# Cell_SARA-G350-02S.net
KiCad netlist of a schematic drawn in Altium Designer
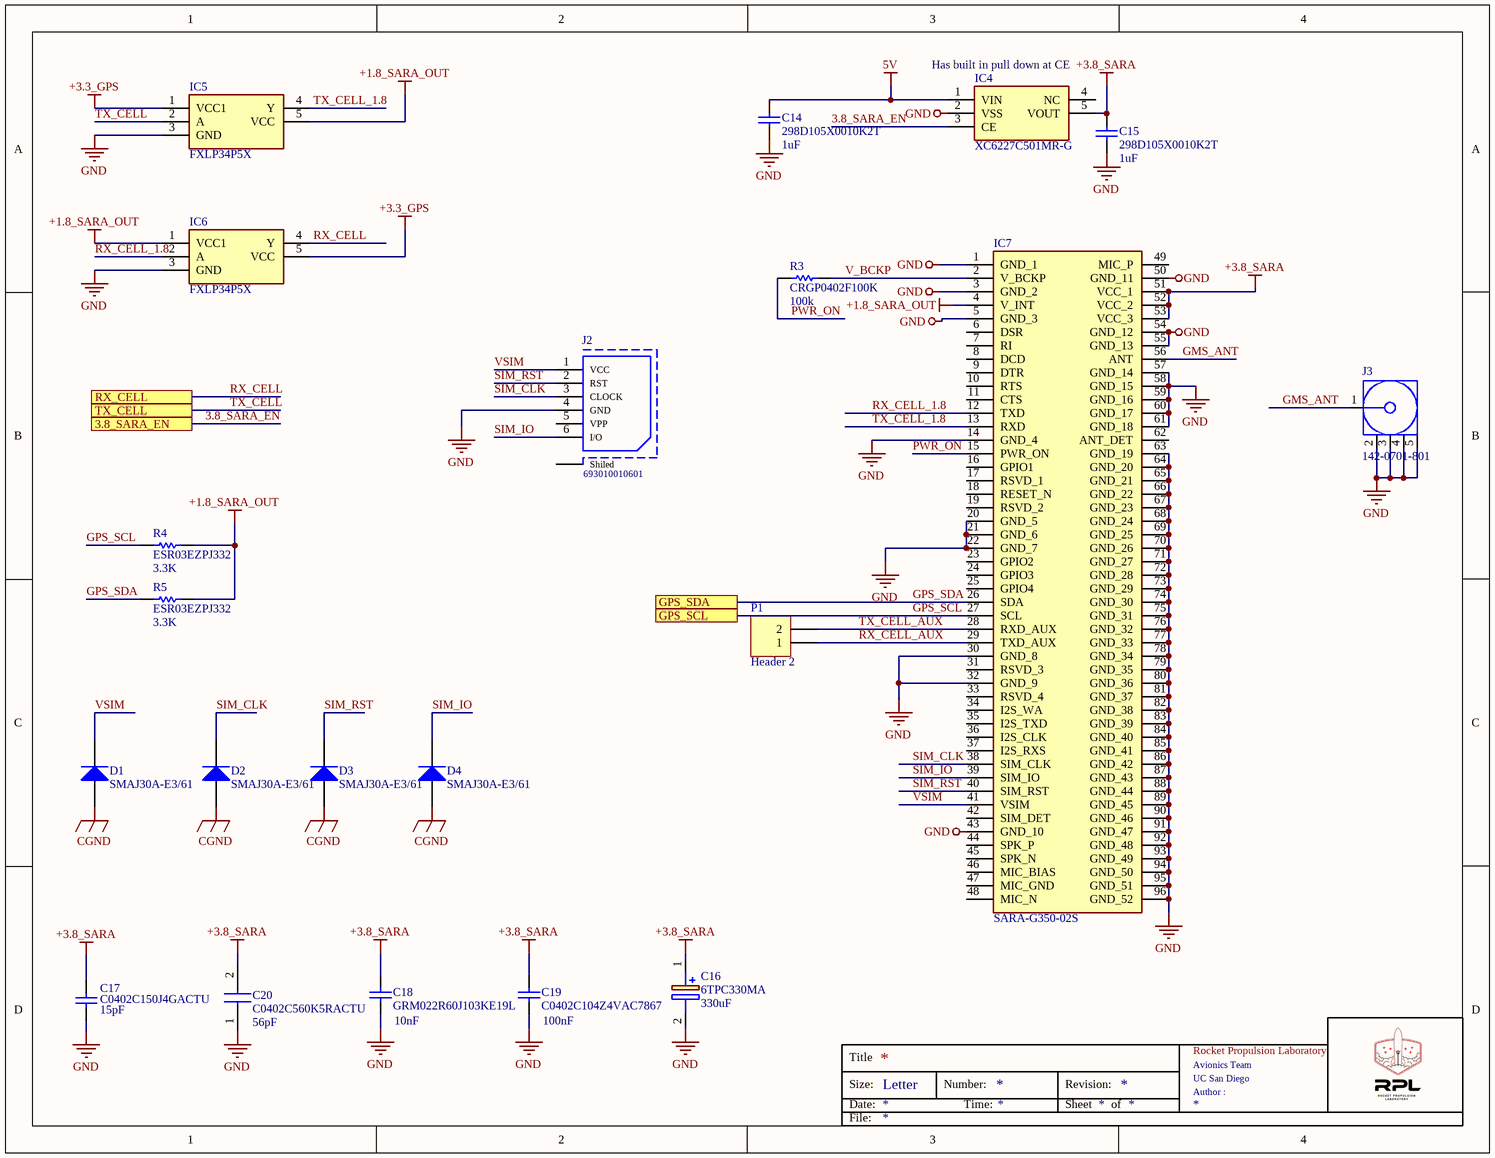
[diagram p0: Cell_SARA-G350-02S.SchDoc]

(export (version "E")
  (design (tool "Eeschema 10.0.6"))
  (components
    (comp (ref "C14")
      (value "298D105X0010K2T")
      (footprint "0402")
      (description "Capacitor")
      (fields (field (name "ALTIUM_VALUE") "1uF") (field (name "PUBLISHER") "Altium Limited"))
      (libsource (lib "Miscellaneous Devices") (part "Cap"))
    )
    (comp (ref "C15")
      (value "298D105X0010K2T")
      (footprint "0402")
      (description "Capacitor")
      (fields (field (name "ALTIUM_VALUE") "1uF") (field (name "PUBLISHER") "Altium Limited"))
      (libsource (lib "Miscellaneous Devices") (part "Cap"))
    )
    (comp (ref "C16")
      (value "6TPC330MA")
      (footprint "PcbLib1:CAPPM7343X200N")
      (description "Capacitor Polarised")
      (fields
        (field (name "MOUSER PART NUMBER") "667-6TPC330MA")
        (field (name "RS PART NUMBER") "7887368P")
        (field (name "SPEC") "330uF")
      )
      (libsource (lib "*") (part "6TPC330MA"))
    )
    (comp (ref "C17")
      (value "C0402C150J4GACTU")
      (footprint "CAPC0402(1005)60_L")
      (description "CAP 15pF 16V ±5% 0402 (1005 Metric) Thickness 0.6mm SMD")
      (fields (field (name "ALTIUM_VALUE") "15pF") (field (name "TOLERANCE") "Â±5%"))
      (libsource (lib "Altium Content Vault") (part "CAP"))
    )
    (comp (ref "C18")
      (value "GRM022R60J103KE19L")
      (footprint "CAPC1005X55X25NL05T10")
      (fields (field (name "MANUFACTURER") "Murata") (field (name "SPEC") "10nF"))
      (libsource (lib "Altium Content Vault") (part "CAP"))
    )
    (comp (ref "C19")
      (value "C0402C104Z4VAC7867")
      (footprint "CAPC1005X60X30LL05T10")
      (fields (field (name "MANUFACTURER") "Kemet") (field (name "SPEC") "100nF"))
      (libsource (lib "Altium Content Vault") (part "CAP"))
    )
    (comp (ref "C20")
      (value "C0402C560K5RACTU")
      (footprint "PcbLib1:CAPC1005X55N")
      (description "Capacitor")
      (fields (field (name "MOUSER PART NUMBER") "80-C0402C560K5RACTU") (field (name "SPEC") "56pF"))
      (libsource (lib "*") (part "C0402C560K5RACTU"))
    )
    (comp (ref "D1")
      (value "SMAJ30A-E3/61")
      (footprint "VISH-DO-214AC-2_N")
      (fields (field (name "MANUFACTURER") "Vishay Semiconductor"))
      (libsource (lib "Altium Content Vault") (part "VISH-K1A2-2"))
    )
    (comp (ref "D2")
      (value "SMAJ30A-E3/61")
      (footprint "VISH-DO-214AC-2_N")
      (fields (field (name "MANUFACTURER") "Vishay Semiconductor"))
      (libsource (lib "Altium Content Vault") (part "VISH-K1A2-2"))
    )
    (comp (ref "D3")
      (value "SMAJ30A-E3/61")
      (footprint "VISH-DO-214AC-2_N")
      (fields (field (name "MANUFACTURER") "Vishay Semiconductor"))
      (libsource (lib "Altium Content Vault") (part "VISH-K1A2-2"))
    )
    (comp (ref "D4")
      (value "SMAJ30A-E3/61")
      (footprint "VISH-DO-214AC-2_N")
      (fields (field (name "MANUFACTURER") "Vishay Semiconductor"))
      (libsource (lib "Altium Content Vault") (part "VISH-K1A2-2"))
    )
    (comp (ref "IC4")
      (value "XC6227C501MR-G")
      (footprint "PcbLib1:SOT95P280X130-5N")
      (description "Integrated Circuit")
      (fields (field (name "MOUSER PART NUMBER") "865-XC6227C501MR-G"))
      (libsource (lib "*") (part "XC6227C501MR-G"))
    )
    (comp (ref "IC5")
      (value "FXLP34P5X")
      (footprint "PcbLib1:SOT65P210X110-5N")
      (description "Integrated Circuit")
      (fields (field (name "MOUSER PART NUMBER") "512-FXLP34P5X"))
      (libsource (lib "*") (part "FXLP34P5X"))
    )
    (comp (ref "IC6")
      (value "FXLP34P5X")
      (footprint "PcbLib1:SOT65P210X110-5N")
      (description "Integrated Circuit")
      (fields (field (name "MOUSER PART NUMBER") "512-FXLP34P5X"))
      (libsource (lib "*") (part "FXLP34P5X"))
    )
    (comp (ref "IC7")
      (value "SARA-G350-02S")
      (footprint "PcbLib1:SARA-G350_1")
      (description "Integrated Circuit")
      (libsource (lib "*") (part "SARA-G350-02S"))
    )
    (comp (ref "J2")
      (value "693010010601")
      (footprint "693010010601")
      (description "WR-CRD Mini SIM Card Connector Header")
      (fields (field (name "MANUFACTURER") "Wurth Elektronik") (field (name "PUBLISHER") "WurthElektronik"))
      (libsource (lib "Altium Content Vault") (part "WE-CN-SD-6-SW-1S"))
    )
    (comp (ref "J3")
      (value "142-0701-801")
      (footprint "CINC-142-0701-801_V")
      (description "SMA End Launch Jack Receptacle, 50 Ohm, 0 to 18 GHz, -65 to 165 degC, 5-Pin SMD, RoHS, Bulk")
      (fields (field (name "MANUFACTURER") "EmersonConnectivitySolutions"))
      (libsource (lib "Altium Content Vault") (part "CN-S-4F-RF5"))
    )
    (comp (ref "P1")
      (value "Header 2")
      (footprint "HDR1X2")
      (description "Header, 2-Pin")
      (fields (field (name "PUBLISHER") "Altium Limited"))
      (libsource (lib "Miscellaneous Connectors") (part "Header 2"))
    )
    (comp (ref "R3")
      (value "CRGP0402F100K")
      (footprint "0402")
      (description "Resistor")
      (fields (field (name "ALTIUM_VALUE") "100k") (field (name "PUBLISHER") "Altium Limited"))
      (libsource (lib "Miscellaneous Devices") (part "Res1"))
    )
    (comp (ref "R4")
      (value "ESR03EZPJ332")
      (footprint "1608[0603]")
      (description "Resistor")
      (fields (field (name "ALTIUM_VALUE") "3.3K") (field (name "PUBLISHER") "Altium Limited"))
      (libsource (lib "Miscellaneous Devices") (part "Res1"))
    )
    (comp (ref "R5")
      (value "ESR03EZPJ332")
      (footprint "1608[0603]")
      (description "Resistor")
      (fields (field (name "ALTIUM_VALUE") "3.3K") (field (name "PUBLISHER") "Altium Limited"))
      (libsource (lib "Miscellaneous Devices") (part "Res1"))
    )
  )
  (nets
    (net (code "1") (name "+1.8_SARA_OUT") (class "Default")
      (node (ref "IC5") (pin "5") (pinfunction "VCC_5") (pintype "passive"))
      (node (ref "IC6") (pin "1") (pinfunction "VCC1_1") (pintype "passive"))
      (node (ref "IC7") (pin "4") (pinfunction "V_INT_4") (pintype "passive"))
      (node (ref "R4") (pin "2") (pinfunction "2_2") (pintype "passive"))
      (node (ref "R5") (pin "2") (pinfunction "2_2") (pintype "passive"))
    )
    (net (code "2") (name "+3.3_GPS") (class "Default")
      (node (ref "IC5") (pin "1") (pinfunction "VCC1_1") (pintype "passive"))
      (node (ref "IC6") (pin "5") (pinfunction "VCC_5") (pintype "passive"))
    )
    (net (code "3") (name "+3.8_SARA") (class "Default")
      (node (ref "C15") (pin "2") (pinfunction "2_2") (pintype "passive"))
      (node (ref "C16") (pin "1") (pinfunction "+_1") (pintype "passive"))
      (node (ref "C17") (pin "2") (pinfunction "2_2") (pintype "passive"))
      (node (ref "C18") (pin "2") (pinfunction "2_2") (pintype "passive"))
      (node (ref "C19") (pin "2") (pinfunction "2_2") (pintype "passive"))
      (node (ref "C20") (pin "2") (pinfunction "2_2") (pintype "passive"))
      (node (ref "IC4") (pin "5") (pinfunction "VOUT_5") (pintype "passive"))
      (node (ref "IC7") (pin "51") (pinfunction "VCC_1_51") (pintype "passive"))
      (node (ref "IC7") (pin "52") (pinfunction "VCC_2_52") (pintype "passive"))
      (node (ref "IC7") (pin "53") (pinfunction "VCC_3_53") (pintype "passive"))
    )
    (net (code "4") (name "/3.8_SARA_EN") (class "Default")
      (node (ref "IC4") (pin "3") (pinfunction "CE_3") (pintype "passive"))
    )
    (net (code "5") (name "/GMS_ANT") (class "Default")
      (node (ref "IC7") (pin "56") (pinfunction "ANT_56") (pintype "passive"))
      (node (ref "J3") (pin "1") (pinfunction "1_1") (pintype "passive"))
    )
    (net (code "6") (name "/GPS_SCL") (class "Default")
      (node (ref "IC7") (pin "27") (pinfunction "SCL_27") (pintype "passive"))
      (node (ref "R4") (pin "1") (pinfunction "1_1") (pintype "passive"))
    )
    (net (code "7") (name "/GPS_SDA") (class "Default")
      (node (ref "IC7") (pin "26") (pinfunction "SDA_26") (pintype "passive"))
      (node (ref "R5") (pin "1") (pinfunction "1_1") (pintype "passive"))
    )
    (net (code "8") (name "/PWR_ON") (class "Default")
      (node (ref "IC7") (pin "15") (pinfunction "PWR_ON_15") (pintype "passive"))
      (node (ref "R3") (pin "2") (pinfunction "2_2") (pintype "passive"))
    )
    (net (code "9") (name "/RX_CELL") (class "Default")
      (node (ref "IC6") (pin "4") (pinfunction "Y_4") (pintype "passive"))
    )
    (net (code "10") (name "/RX_CELL_1.8") (class "Default")
      (node (ref "IC6") (pin "2") (pinfunction "A_2") (pintype "passive"))
      (node (ref "IC7") (pin "12") (pinfunction "TXD_12") (pintype "passive"))
    )
    (net (code "11") (name "/RX_CELL_AUX") (class "Default")
      (node (ref "IC7") (pin "29") (pinfunction "TXD_AUX_29") (pintype "passive"))
      (node (ref "P1") (pin "1") (pinfunction "1_1") (pintype "passive"))
    )
    (net (code "12") (name "/SIM_CLK") (class "Default")
      (node (ref "D2") (pin "1") (pinfunction "K_1") (pintype "passive"))
      (node (ref "IC7") (pin "38") (pinfunction "SIM_CLK_38") (pintype "passive"))
      (node (ref "J2") (pin "3") (pinfunction "CLOCK_3") (pintype "passive"))
    )
    (net (code "13") (name "/SIM_IO") (class "Default")
      (node (ref "D4") (pin "1") (pinfunction "K_1") (pintype "passive"))
      (node (ref "IC7") (pin "39") (pinfunction "SIM_IO_39") (pintype "passive"))
      (node (ref "J2") (pin "6") (pinfunction "I/O_6") (pintype "passive"))
    )
    (net (code "14") (name "/SIM_RST") (class "Default")
      (node (ref "D3") (pin "1") (pinfunction "K_1") (pintype "passive"))
      (node (ref "IC7") (pin "40") (pinfunction "SIM_RST_40") (pintype "passive"))
      (node (ref "J2") (pin "2") (pinfunction "RST_2") (pintype "passive"))
    )
    (net (code "15") (name "/TX_CELL") (class "Default")
      (node (ref "IC5") (pin "2") (pinfunction "A_2") (pintype "passive"))
    )
    (net (code "16") (name "/TX_CELL_1.8") (class "Default")
      (node (ref "IC5") (pin "4") (pinfunction "Y_4") (pintype "passive"))
      (node (ref "IC7") (pin "13") (pinfunction "RXD_13") (pintype "passive"))
    )
    (net (code "17") (name "/TX_CELL_AUX") (class "Default")
      (node (ref "IC7") (pin "28") (pinfunction "RXD_AUX_28") (pintype "passive"))
      (node (ref "P1") (pin "2") (pinfunction "2_2") (pintype "passive"))
    )
    (net (code "18") (name "/VSIM") (class "Default")
      (node (ref "D1") (pin "1") (pinfunction "K_1") (pintype "passive"))
      (node (ref "IC7") (pin "41") (pinfunction "VSIM_41") (pintype "passive"))
      (node (ref "J2") (pin "1") (pinfunction "VCC_1") (pintype "passive"))
    )
    (net (code "19") (name "/V_BCKP") (class "Default")
      (node (ref "IC7") (pin "2") (pinfunction "V_BCKP_2") (pintype "passive"))
      (node (ref "R3") (pin "1") (pinfunction "1_1") (pintype "passive"))
    )
    (net (code "20") (name "5V") (class "Default")
      (node (ref "C14") (pin "2") (pinfunction "2_2") (pintype "passive"))
      (node (ref "IC4") (pin "1") (pinfunction "VIN_1") (pintype "passive"))
    )
    (net (code "21") (name "CGND") (class "Default")
      (node (ref "D1") (pin "2") (pinfunction "A_2") (pintype "passive"))
      (node (ref "D2") (pin "2") (pinfunction "A_2") (pintype "passive"))
      (node (ref "D3") (pin "2") (pinfunction "A_2") (pintype "passive"))
      (node (ref "D4") (pin "2") (pinfunction "A_2") (pintype "passive"))
    )
    (net (code "22") (name "GND") (class "Default")
      (node (ref "C14") (pin "1") (pinfunction "1_1") (pintype "passive"))
      (node (ref "C15") (pin "1") (pinfunction "1_1") (pintype "passive"))
      (node (ref "C16") (pin "2") (pinfunction "-_2") (pintype "passive"))
      (node (ref "C17") (pin "1") (pinfunction "1_1") (pintype "passive"))
      (node (ref "C18") (pin "1") (pinfunction "1_1") (pintype "passive"))
      (node (ref "C19") (pin "1") (pinfunction "1_1") (pintype "passive"))
      (node (ref "C20") (pin "1") (pinfunction "1_1") (pintype "passive"))
      (node (ref "IC4") (pin "2") (pinfunction "VSS_2") (pintype "passive"))
      (node (ref "IC5") (pin "3") (pinfunction "GND_3") (pintype "passive"))
      (node (ref "IC6") (pin "3") (pinfunction "GND_3") (pintype "passive"))
      (node (ref "IC7") (pin "1") (pinfunction "GND_1_1") (pintype "passive"))
      (node (ref "IC7") (pin "14") (pinfunction "GND_4_14") (pintype "passive"))
      (node (ref "IC7") (pin "20") (pinfunction "GND_5_20") (pintype "passive"))
      (node (ref "IC7") (pin "21") (pinfunction "GND_6_21") (pintype "passive"))
      (node (ref "IC7") (pin "22") (pinfunction "GND_7_22") (pintype "passive"))
      (node (ref "IC7") (pin "3") (pinfunction "GND_2_3") (pintype "passive"))
      (node (ref "IC7") (pin "30") (pinfunction "GND_8_30") (pintype "passive"))
      (node (ref "IC7") (pin "32") (pinfunction "GND_9_32") (pintype "passive"))
      (node (ref "IC7") (pin "43") (pinfunction "GND_10_43") (pintype "passive"))
      (node (ref "IC7") (pin "5") (pinfunction "GND_3_5") (pintype "passive"))
      (node (ref "IC7") (pin "50") (pinfunction "GND_11_50") (pintype "passive"))
      (node (ref "IC7") (pin "54") (pinfunction "GND_12_54") (pintype "passive"))
      (node (ref "IC7") (pin "55") (pinfunction "GND_13_55") (pintype "passive"))
      (node (ref "IC7") (pin "57") (pinfunction "GND_14_57") (pintype "passive"))
      (node (ref "IC7") (pin "58") (pinfunction "GND_15_58") (pintype "passive"))
      (node (ref "IC7") (pin "59") (pinfunction "GND_16_59") (pintype "passive"))
      (node (ref "IC7") (pin "60") (pinfunction "GND_17_60") (pintype "passive"))
      (node (ref "IC7") (pin "61") (pinfunction "GND_18_61") (pintype "passive"))
      (node (ref "IC7") (pin "63") (pinfunction "GND_19_63") (pintype "passive"))
      (node (ref "IC7") (pin "64") (pinfunction "GND_20_64") (pintype "passive"))
      (node (ref "IC7") (pin "65") (pinfunction "GND_21_65") (pintype "passive"))
      (node (ref "IC7") (pin "66") (pinfunction "GND_22_66") (pintype "passive"))
      (node (ref "IC7") (pin "67") (pinfunction "GND_23_67") (pintype "passive"))
      (node (ref "IC7") (pin "68") (pinfunction "GND_24_68") (pintype "passive"))
      (node (ref "IC7") (pin "69") (pinfunction "GND_25_69") (pintype "passive"))
      (node (ref "IC7") (pin "70") (pinfunction "GND_26_70") (pintype "passive"))
      (node (ref "IC7") (pin "71") (pinfunction "GND_27_71") (pintype "passive"))
      (node (ref "IC7") (pin "72") (pinfunction "GND_28_72") (pintype "passive"))
      (node (ref "IC7") (pin "73") (pinfunction "GND_29_73") (pintype "passive"))
      (node (ref "IC7") (pin "74") (pinfunction "GND_30_74") (pintype "passive"))
      (node (ref "IC7") (pin "75") (pinfunction "GND_31_75") (pintype "passive"))
      (node (ref "IC7") (pin "76") (pinfunction "GND_32_76") (pintype "passive"))
      (node (ref "IC7") (pin "77") (pinfunction "GND_33_77") (pintype "passive"))
      (node (ref "IC7") (pin "78") (pinfunction "GND_34_78") (pintype "passive"))
      (node (ref "IC7") (pin "79") (pinfunction "GND_35_79") (pintype "passive"))
      (node (ref "IC7") (pin "80") (pinfunction "GND_36_80") (pintype "passive"))
      (node (ref "IC7") (pin "81") (pinfunction "GND_37_81") (pintype "passive"))
      (node (ref "IC7") (pin "82") (pinfunction "GND_38_82") (pintype "passive"))
      (node (ref "IC7") (pin "83") (pinfunction "GND_39_83") (pintype "passive"))
      (node (ref "IC7") (pin "84") (pinfunction "GND_40_84") (pintype "passive"))
      (node (ref "IC7") (pin "85") (pinfunction "GND_41_85") (pintype "passive"))
      (node (ref "IC7") (pin "86") (pinfunction "GND_42_86") (pintype "passive"))
      (node (ref "IC7") (pin "87") (pinfunction "GND_43_87") (pintype "passive"))
      (node (ref "IC7") (pin "88") (pinfunction "GND_44_88") (pintype "passive"))
      (node (ref "IC7") (pin "89") (pinfunction "GND_45_89") (pintype "passive"))
      (node (ref "IC7") (pin "90") (pinfunction "GND_46_90") (pintype "passive"))
      (node (ref "IC7") (pin "91") (pinfunction "GND_47_91") (pintype "passive"))
      (node (ref "IC7") (pin "92") (pinfunction "GND_48_92") (pintype "passive"))
      (node (ref "IC7") (pin "93") (pinfunction "GND_49_93") (pintype "passive"))
      (node (ref "IC7") (pin "94") (pinfunction "GND_50_94") (pintype "passive"))
      (node (ref "IC7") (pin "95") (pinfunction "GND_51_95") (pintype "passive"))
      (node (ref "IC7") (pin "96") (pinfunction "GND_52_96") (pintype "passive"))
      (node (ref "J2") (pin "4") (pinfunction "GND_4") (pintype "passive"))
      (node (ref "J3") (pin "2") (pinfunction "2_2") (pintype "passive"))
      (node (ref "J3") (pin "3") (pinfunction "3_3") (pintype "passive"))
      (node (ref "J3") (pin "4") (pinfunction "4_4") (pintype "passive"))
      (node (ref "J3") (pin "5") (pinfunction "5_5") (pintype "passive"))
    )
    (net (code "23") (name "unconnected-(IC4-NC-Pad4)") (class "Default")
      (node (ref "IC4") (pin "4") (pinfunction "NC_4") (pintype "passive"))
    )
    (net (code "24") (name "unconnected-(IC7-ANT_DET-Pad62)") (class "Default")
      (node (ref "IC7") (pin "62") (pinfunction "ANT_DET_62") (pintype "passive"))
    )
    (net (code "25") (name "unconnected-(IC7-CTS-Pad11)") (class "Default")
      (node (ref "IC7") (pin "11") (pinfunction "CTS_11") (pintype "passive"))
    )
    (net (code "26") (name "unconnected-(IC7-DCD-Pad8)") (class "Default")
      (node (ref "IC7") (pin "8") (pinfunction "DCD_8") (pintype "passive"))
    )
    (net (code "27") (name "unconnected-(IC7-DSR-Pad6)") (class "Default")
      (node (ref "IC7") (pin "6") (pinfunction "DSR_6") (pintype "passive"))
    )
    (net (code "28") (name "unconnected-(IC7-DTR-Pad9)") (class "Default")
      (node (ref "IC7") (pin "9") (pinfunction "DTR_9") (pintype "passive"))
    )
    (net (code "29") (name "unconnected-(IC7-GPIO1-Pad16)") (class "Default")
      (node (ref "IC7") (pin "16") (pinfunction "GPIO1_16") (pintype "passive"))
    )
    (net (code "30") (name "unconnected-(IC7-GPIO2-Pad23)") (class "Default")
      (node (ref "IC7") (pin "23") (pinfunction "GPIO2_23") (pintype "passive"))
    )
    (net (code "31") (name "unconnected-(IC7-GPIO3-Pad24)") (class "Default")
      (node (ref "IC7") (pin "24") (pinfunction "GPIO3_24") (pintype "passive"))
    )
    (net (code "32") (name "unconnected-(IC7-GPIO4-Pad25)") (class "Default")
      (node (ref "IC7") (pin "25") (pinfunction "GPIO4_25") (pintype "passive"))
    )
    (net (code "33") (name "unconnected-(IC7-I2S_CLK-Pad36)") (class "Default")
      (node (ref "IC7") (pin "36") (pinfunction "I2S_CLK_36") (pintype "passive"))
    )
    (net (code "34") (name "unconnected-(IC7-I2S_RXS-Pad37)") (class "Default")
      (node (ref "IC7") (pin "37") (pinfunction "I2S_RXS_37") (pintype "passive"))
    )
    (net (code "35") (name "unconnected-(IC7-I2S_TXD-Pad35)") (class "Default")
      (node (ref "IC7") (pin "35") (pinfunction "I2S_TXD_35") (pintype "passive"))
    )
    (net (code "36") (name "unconnected-(IC7-I2S_WA-Pad34)") (class "Default")
      (node (ref "IC7") (pin "34") (pinfunction "I2S_WA_34") (pintype "passive"))
    )
    (net (code "37") (name "unconnected-(IC7-MIC_BIAS-Pad46)") (class "Default")
      (node (ref "IC7") (pin "46") (pinfunction "MIC_BIAS_46") (pintype "passive"))
    )
    (net (code "38") (name "unconnected-(IC7-MIC_GND-Pad47)") (class "Default")
      (node (ref "IC7") (pin "47") (pinfunction "MIC_GND_47") (pintype "passive"))
    )
    (net (code "39") (name "unconnected-(IC7-MIC_N-Pad48)") (class "Default")
      (node (ref "IC7") (pin "48") (pinfunction "MIC_N_48") (pintype "passive"))
    )
    (net (code "40") (name "unconnected-(IC7-MIC_P-Pad49)") (class "Default")
      (node (ref "IC7") (pin "49") (pinfunction "MIC_P_49") (pintype "passive"))
    )
    (net (code "41") (name "unconnected-(IC7-RESET_N-Pad18)") (class "Default")
      (node (ref "IC7") (pin "18") (pinfunction "RESET_N_18") (pintype "passive"))
    )
    (net (code "42") (name "unconnected-(IC7-RI-Pad7)") (class "Default")
      (node (ref "IC7") (pin "7") (pinfunction "RI_7") (pintype "passive"))
    )
    (net (code "43") (name "unconnected-(IC7-RSVD_1-Pad17)") (class "Default")
      (node (ref "IC7") (pin "17") (pinfunction "RSVD_1_17") (pintype "passive"))
    )
    (net (code "44") (name "unconnected-(IC7-RSVD_2-Pad19)") (class "Default")
      (node (ref "IC7") (pin "19") (pinfunction "RSVD_2_19") (pintype "passive"))
    )
    (net (code "45") (name "unconnected-(IC7-RSVD_3-Pad31)") (class "Default")
      (node (ref "IC7") (pin "31") (pinfunction "RSVD_3_31") (pintype "passive"))
    )
    (net (code "46") (name "unconnected-(IC7-RSVD_4-Pad33)") (class "Default")
      (node (ref "IC7") (pin "33") (pinfunction "RSVD_4_33") (pintype "passive"))
    )
    (net (code "47") (name "unconnected-(IC7-RTS-Pad10)") (class "Default")
      (node (ref "IC7") (pin "10") (pinfunction "RTS_10") (pintype "passive"))
    )
    (net (code "48") (name "unconnected-(IC7-SIM_DET-Pad42)") (class "Default")
      (node (ref "IC7") (pin "42") (pinfunction "SIM_DET_42") (pintype "passive"))
    )
    (net (code "49") (name "unconnected-(IC7-SPK_N-Pad45)") (class "Default")
      (node (ref "IC7") (pin "45") (pinfunction "SPK_N_45") (pintype "passive"))
    )
    (net (code "50") (name "unconnected-(IC7-SPK_P-Pad44)") (class "Default")
      (node (ref "IC7") (pin "44") (pinfunction "SPK_P_44") (pintype "passive"))
    )
    (net (code "51") (name "unconnected-(J2-PadShiled)") (class "Default")
      (node (ref "J2") (pin "Shiled") (pinfunction "Shiled_Shiled") (pintype "passive"))
    )
    (net (code "52") (name "unconnected-(J2-VPP-Pad5)") (class "Default")
      (node (ref "J2") (pin "5") (pinfunction "VPP_5") (pintype "passive"))
    )
  )
)
